# memtester.net
KiCad netlist of a schematic drawn in EAGLE
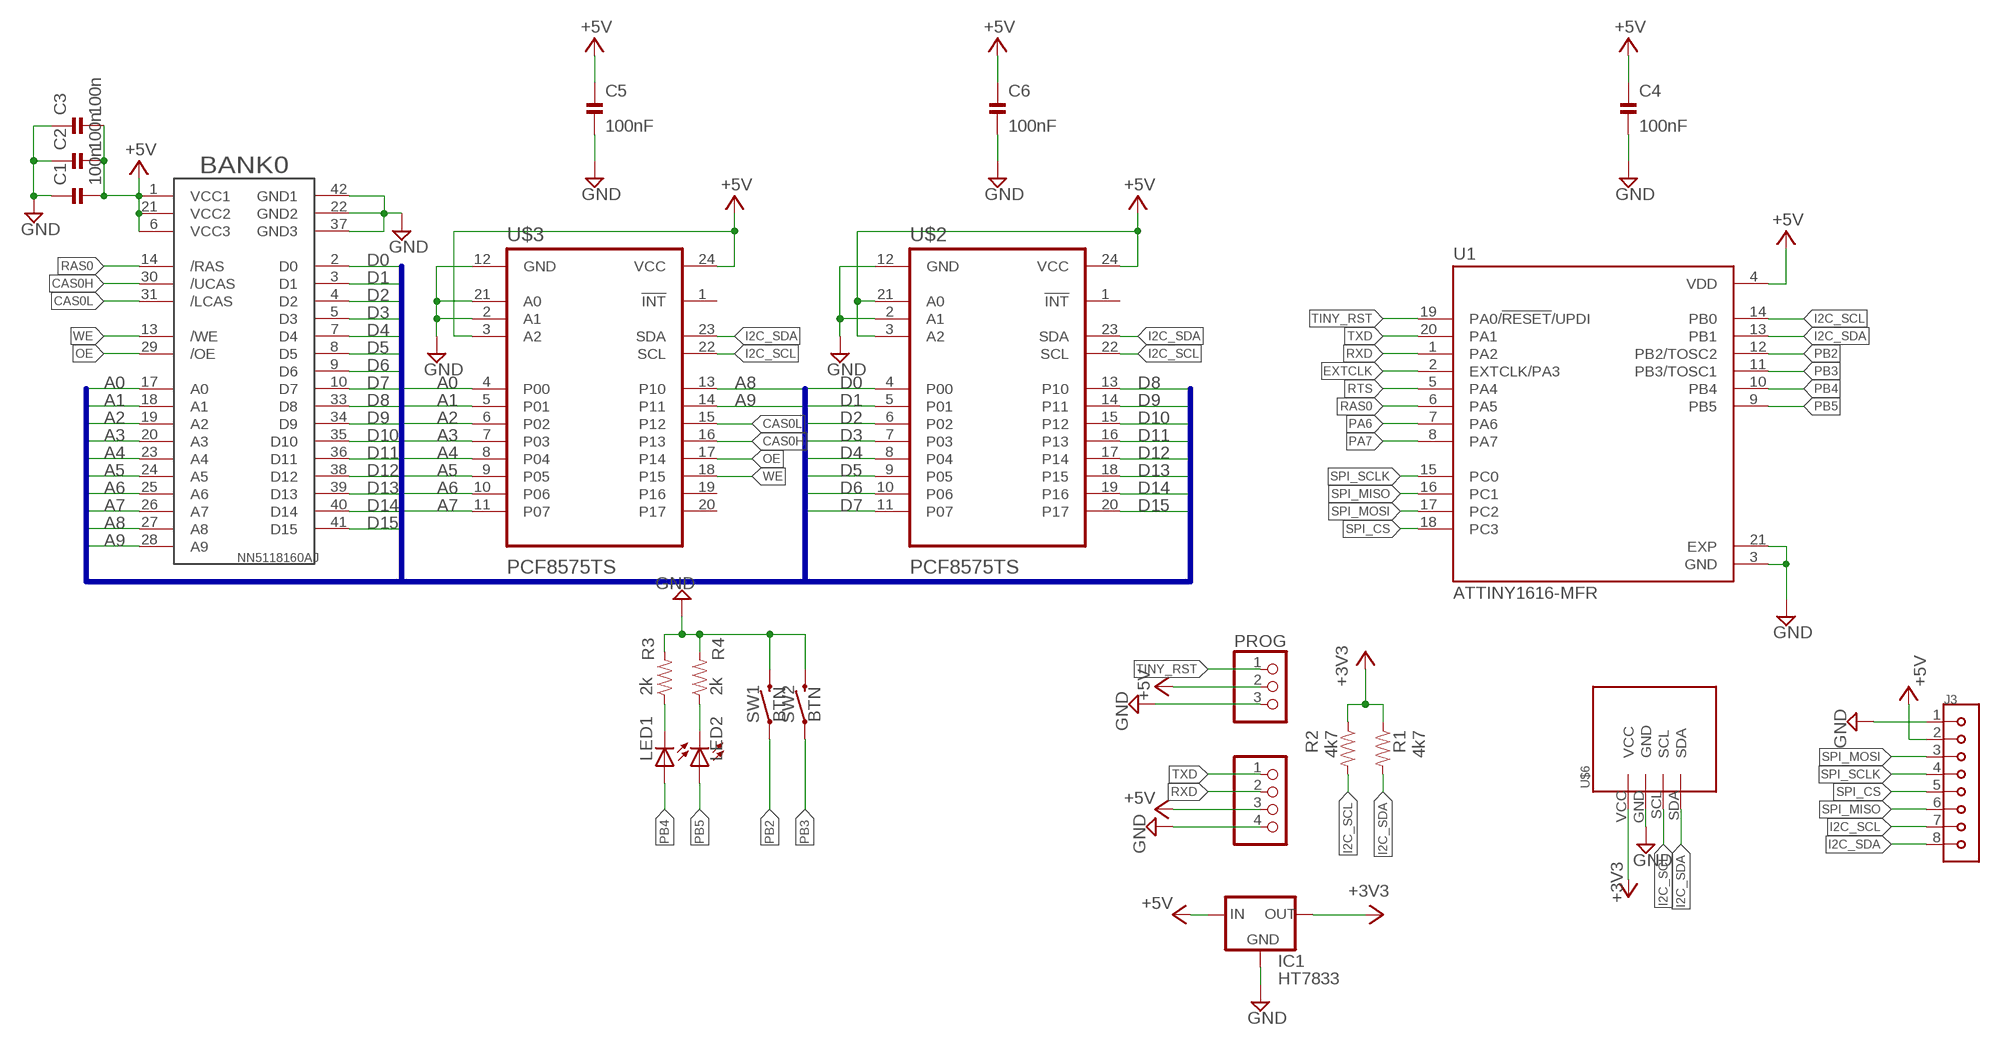
[diagram p0: schematic, sheet 1]

(export (version "E")
  (design (tool "Eeschema 10.0.6"))
  (components
    (comp (ref "C1")
      (value "100n")
      (footprint "eagle-import:0402_CAP")
      (libsource (lib "eagle-import") (part "CAPACITOR0402_CAP"))
    )
    (comp (ref "C2")
      (value "100n")
      (footprint "eagle-import:0402_CAP")
      (libsource (lib "eagle-import") (part "CAPACITOR0402_CAP"))
    )
    (comp (ref "C3")
      (value "100n")
      (footprint "eagle-import:0402_CAP")
      (libsource (lib "eagle-import") (part "CAPACITOR0402_CAP"))
    )
    (comp (ref "C4")
      (value "100nF")
      (footprint "eagle-import:0402_CAP")
      (libsource (lib "eagle-import") (part "CAPACITOR0402_CAP"))
    )
    (comp (ref "C5")
      (value "100nF")
      (footprint "eagle-import:0402_CAP")
      (libsource (lib "eagle-import") (part "CAPACITOR0402_CAP"))
    )
    (comp (ref "C6")
      (value "100nF")
      (footprint "eagle-import:0402_CAP")
      (libsource (lib "eagle-import") (part "CAPACITOR0402_CAP"))
    )
    (comp (ref "IC1")
      (value "HT7833")
      (footprint "eagle-import:SOT-89")
      (fields (field (name "LCSC_PART") "C50936"))
      (libsource (lib "eagle-import") (part "HT7333"))
    )
    (comp (ref "J3")
      (value "SM08B-SRSS-TB(LF)(SN)")
      (footprint "eagle-import:JST_SM08B-SRSS-TB(LF)(SN)")
      (fields (field (name "MF") "JST Sales") (field (name "LCSC_PART") "C160407"))
      (libsource (lib "eagle-import") (part "SM08B-SRSS-TB(LF)(SN)"))
    )
    (comp (ref "LED1")
      (value "green")
      (footprint "eagle-import:CHIP-LED0805")
      (fields (field (name "LCSC_PART") "C2297"))
      (libsource (lib "eagle-import") (part "LEDCHIP-LED0805"))
    )
    (comp (ref "LED2")
      (value "green")
      (footprint "eagle-import:CHIP-LED0805")
      (fields (field (name "LCSC_PART") "C2297"))
      (libsource (lib "eagle-import") (part "LEDCHIP-LED0805"))
    )
    (comp (ref "PROG")
      (value "PINHD-1X3")
      (footprint "eagle-import:1X03")
      (libsource (lib "eagle-import") (part "PINHD-1X3"))
    )
    (comp (ref "R1")
      (value "4k7")
      (footprint "eagle-import:0402_RES")
      (libsource (lib "eagle-import") (part "RESISTOR0402_RES"))
    )
    (comp (ref "R2")
      (value "4k7")
      (footprint "eagle-import:0402_RES")
      (libsource (lib "eagle-import") (part "RESISTOR0402_RES"))
    )
    (comp (ref "R3")
      (value "2k")
      (footprint "eagle-import:0402_RES")
      (libsource (lib "eagle-import") (part "RESISTOR0402_RES"))
    )
    (comp (ref "R4")
      (value "2k")
      (footprint "eagle-import:0402_RES")
      (libsource (lib "eagle-import") (part "RESISTOR0402_RES"))
    )
    (comp (ref "SW1")
      (value "BTN")
      (footprint "eagle-import:TACTILE_SWITCH_SMD_6.0X3.5MM")
      (fields (field (name "LCSC_PART") "C118141"))
      (libsource (lib "eagle-import") (part "MOMENTARY-SWITCH-SPST-SMD-6.0X3.5MM"))
    )
    (comp (ref "SW2")
      (value "BTN")
      (footprint "eagle-import:TACTILE_SWITCH_SMD_6.0X3.5MM")
      (fields (field (name "LCSC_PART") "C118141"))
      (libsource (lib "eagle-import") (part "MOMENTARY-SWITCH-SPST-SMD-6.0X3.5MM"))
    )
    (comp (ref "U$1")
      (value "NN5118160AJSOCKET")
      (footprint "eagle-import:SOJ42SOCKET")
      (libsource (lib "eagle-import") (part "NN5118160AJSOCKET"))
    )
    (comp (ref "U$2")
      (value "PCF8575TS")
      (footprint "eagle-import:SSOP24")
      (fields (field (name "LCSC_PART") "C12251"))
      (libsource (lib "eagle-import") (part "PCF8575TS"))
    )
    (comp (ref "U$3")
      (value "PCF8575TS")
      (footprint "eagle-import:SSOP24")
      (fields (field (name "LCSC_PART") "C12251"))
      (libsource (lib "eagle-import") (part "PCF8575TS"))
    )
    (comp (ref "U$6")
      (value "OLED_0.96_I2CNO_DRILL")
      (footprint "eagle-import:OLED_0.96_I2C_NO_DRILL")
      (libsource (lib "eagle-import") (part "OLED_0.96_I2CNO_DRILL"))
    )
    (comp (ref "U1")
      (value "ATTINY1616-MFR")
      (footprint "eagle-import:QFN40P300X300X90-21N")
      (fields (field (name "MF") "Microchip"))
      (libsource (lib "eagle-import") (part "ATTINY1616-MFR"))
    )
    (comp (ref "UART")
      (value "PINHD-1X4")
      (footprint "eagle-import:1X04")
      (libsource (lib "eagle-import") (part "PINHD-1X4"))
    )
  )
  (nets
    (net (code "1") (name "+3V3") (class "Default")
      (node (ref "IC1") (pin "1") (pinfunction "OUT_1") (pintype "passive"))
      (node (ref "R1") (pin "1") (pinfunction "1_1") (pintype "passive"))
      (node (ref "R2") (pin "1") (pinfunction "1_1") (pintype "passive"))
      (node (ref "U$6") (pin "VCC") (pinfunction "VCC_VCC") (pintype "bidirectional"))
    )
    (net (code "2") (name "+5V") (class "Default")
      (node (ref "C1") (pin "2") (pinfunction "2_2") (pintype "bidirectional"))
      (node (ref "C2") (pin "2") (pinfunction "2_2") (pintype "bidirectional"))
      (node (ref "C3") (pin "2") (pinfunction "2_2") (pintype "bidirectional"))
      (node (ref "C4") (pin "1") (pinfunction "1_1") (pintype "bidirectional"))
      (node (ref "C5") (pin "1") (pinfunction "1_1") (pintype "bidirectional"))
      (node (ref "C6") (pin "1") (pinfunction "1_1") (pintype "bidirectional"))
      (node (ref "IC1") (pin "3") (pinfunction "IN_3") (pintype "input"))
      (node (ref "IC1") (pin "4") (pinfunction "IN_4") (pintype "input"))
      (node (ref "J3") (pin "2") (pinfunction "2_2") (pintype "passive"))
      (node (ref "PROG") (pin "2") (pinfunction "2_2") (pintype "passive"))
      (node (ref "U$1") (pin "1") (pinfunction "VCC1_1") (pintype "bidirectional"))
      (node (ref "U$1") (pin "21") (pinfunction "VCC2_21") (pintype "bidirectional"))
      (node (ref "U$1") (pin "6") (pinfunction "VCC3_6") (pintype "bidirectional"))
      (node (ref "U$2") (pin "21") (pinfunction "A0_21") (pintype "input"))
      (node (ref "U$2") (pin "24") (pinfunction "VCC_24") (pintype "power_in"))
      (node (ref "U$2") (pin "3") (pinfunction "A2_3") (pintype "input"))
      (node (ref "U$3") (pin "24") (pinfunction "VCC_24") (pintype "power_in"))
      (node (ref "U$3") (pin "3") (pinfunction "A2_3") (pintype "input"))
      (node (ref "U1") (pin "4") (pinfunction "VDD_4") (pintype "power_in"))
      (node (ref "UART") (pin "3") (pinfunction "3_3") (pintype "passive"))
    )
    (net (code "3") (name "/A0") (class "Default")
      (node (ref "U$1") (pin "17") (pinfunction "A0_17") (pintype "bidirectional"))
      (node (ref "U$3") (pin "4") (pinfunction "P00_4") (pintype "bidirectional"))
    )
    (net (code "4") (name "/A1") (class "Default")
      (node (ref "U$1") (pin "18") (pinfunction "A1_18") (pintype "bidirectional"))
      (node (ref "U$3") (pin "5") (pinfunction "P01_5") (pintype "bidirectional"))
    )
    (net (code "5") (name "/A2") (class "Default")
      (node (ref "U$1") (pin "19") (pinfunction "A2_19") (pintype "bidirectional"))
      (node (ref "U$3") (pin "6") (pinfunction "P02_6") (pintype "bidirectional"))
    )
    (net (code "6") (name "/A3") (class "Default")
      (node (ref "U$1") (pin "20") (pinfunction "A3_20") (pintype "bidirectional"))
      (node (ref "U$3") (pin "7") (pinfunction "P03_7") (pintype "bidirectional"))
    )
    (net (code "7") (name "/A4") (class "Default")
      (node (ref "U$1") (pin "23") (pinfunction "A4_23") (pintype "bidirectional"))
      (node (ref "U$3") (pin "8") (pinfunction "P04_8") (pintype "bidirectional"))
    )
    (net (code "8") (name "/A5") (class "Default")
      (node (ref "U$1") (pin "24") (pinfunction "A5_24") (pintype "bidirectional"))
      (node (ref "U$3") (pin "9") (pinfunction "P05_9") (pintype "bidirectional"))
    )
    (net (code "9") (name "/A6") (class "Default")
      (node (ref "U$1") (pin "25") (pinfunction "A6_25") (pintype "bidirectional"))
      (node (ref "U$3") (pin "10") (pinfunction "P06_10") (pintype "bidirectional"))
    )
    (net (code "10") (name "/A7") (class "Default")
      (node (ref "U$1") (pin "26") (pinfunction "A7_26") (pintype "bidirectional"))
      (node (ref "U$3") (pin "11") (pinfunction "P07_11") (pintype "bidirectional"))
    )
    (net (code "11") (name "/A8") (class "Default")
      (node (ref "U$1") (pin "27") (pinfunction "A8_27") (pintype "bidirectional"))
      (node (ref "U$3") (pin "13") (pinfunction "P10_13") (pintype "bidirectional"))
    )
    (net (code "12") (name "/A9") (class "Default")
      (node (ref "U$1") (pin "28") (pinfunction "A9_28") (pintype "bidirectional"))
      (node (ref "U$3") (pin "14") (pinfunction "P11_14") (pintype "bidirectional"))
    )
    (net (code "13") (name "/D0") (class "Default")
      (node (ref "U$1") (pin "2") (pinfunction "D0_2") (pintype "bidirectional"))
      (node (ref "U$2") (pin "4") (pinfunction "P00_4") (pintype "bidirectional"))
    )
    (net (code "14") (name "/D1") (class "Default")
      (node (ref "U$1") (pin "3") (pinfunction "D1_3") (pintype "bidirectional"))
      (node (ref "U$2") (pin "5") (pinfunction "P01_5") (pintype "bidirectional"))
    )
    (net (code "15") (name "/D2") (class "Default")
      (node (ref "U$1") (pin "4") (pinfunction "D2_4") (pintype "bidirectional"))
      (node (ref "U$2") (pin "6") (pinfunction "P02_6") (pintype "bidirectional"))
    )
    (net (code "16") (name "/D3") (class "Default")
      (node (ref "U$1") (pin "5") (pinfunction "D3_5") (pintype "bidirectional"))
      (node (ref "U$2") (pin "7") (pinfunction "P03_7") (pintype "bidirectional"))
    )
    (net (code "17") (name "/D4") (class "Default")
      (node (ref "U$1") (pin "7") (pinfunction "D4_7") (pintype "bidirectional"))
      (node (ref "U$2") (pin "8") (pinfunction "P04_8") (pintype "bidirectional"))
    )
    (net (code "18") (name "/D5") (class "Default")
      (node (ref "U$1") (pin "8") (pinfunction "D5_8") (pintype "bidirectional"))
      (node (ref "U$2") (pin "9") (pinfunction "P05_9") (pintype "bidirectional"))
    )
    (net (code "19") (name "/D6") (class "Default")
      (node (ref "U$1") (pin "9") (pinfunction "D6_9") (pintype "bidirectional"))
      (node (ref "U$2") (pin "10") (pinfunction "P06_10") (pintype "bidirectional"))
    )
    (net (code "20") (name "/D7") (class "Default")
      (node (ref "U$1") (pin "10") (pinfunction "D7_10") (pintype "bidirectional"))
      (node (ref "U$2") (pin "11") (pinfunction "P07_11") (pintype "bidirectional"))
    )
    (net (code "21") (name "/D8") (class "Default")
      (node (ref "U$1") (pin "33") (pinfunction "D8_33") (pintype "bidirectional"))
      (node (ref "U$2") (pin "13") (pinfunction "P10_13") (pintype "bidirectional"))
    )
    (net (code "22") (name "/D9") (class "Default")
      (node (ref "U$1") (pin "34") (pinfunction "D9_34") (pintype "bidirectional"))
      (node (ref "U$2") (pin "14") (pinfunction "P11_14") (pintype "bidirectional"))
    )
    (net (code "23") (name "/D10") (class "Default")
      (node (ref "U$1") (pin "35") (pinfunction "D10_35") (pintype "bidirectional"))
      (node (ref "U$2") (pin "15") (pinfunction "P12_15") (pintype "bidirectional"))
    )
    (net (code "24") (name "/D11") (class "Default")
      (node (ref "U$1") (pin "36") (pinfunction "D11_36") (pintype "bidirectional"))
      (node (ref "U$2") (pin "16") (pinfunction "P13_16") (pintype "bidirectional"))
    )
    (net (code "25") (name "/D12") (class "Default")
      (node (ref "U$1") (pin "38") (pinfunction "D12_38") (pintype "bidirectional"))
      (node (ref "U$2") (pin "17") (pinfunction "P14_17") (pintype "bidirectional"))
    )
    (net (code "26") (name "/D13") (class "Default")
      (node (ref "U$1") (pin "39") (pinfunction "D13_39") (pintype "bidirectional"))
      (node (ref "U$2") (pin "18") (pinfunction "P15_18") (pintype "bidirectional"))
    )
    (net (code "27") (name "/D14") (class "Default")
      (node (ref "U$1") (pin "40") (pinfunction "D14_40") (pintype "bidirectional"))
      (node (ref "U$2") (pin "19") (pinfunction "P16_19") (pintype "bidirectional"))
    )
    (net (code "28") (name "/D15") (class "Default")
      (node (ref "U$1") (pin "41") (pinfunction "D15_41") (pintype "bidirectional"))
      (node (ref "U$2") (pin "20") (pinfunction "P17_20") (pintype "bidirectional"))
    )
    (net (code "29") (name "CAS0H") (class "Default")
      (node (ref "U$1") (pin "30") (pinfunction "/UCAS_30") (pintype "bidirectional"))
      (node (ref "U$3") (pin "16") (pinfunction "P13_16") (pintype "bidirectional"))
    )
    (net (code "30") (name "CAS0L") (class "Default")
      (node (ref "U$1") (pin "31") (pinfunction "/LCAS_31") (pintype "bidirectional"))
      (node (ref "U$3") (pin "15") (pinfunction "P12_15") (pintype "bidirectional"))
    )
    (net (code "31") (name "EXTCLK") (class "Default")
      (node (ref "U1") (pin "2") (pinfunction "EXTCLK/PA3_2") (pintype "bidirectional"))
    )
    (net (code "32") (name "GND") (class "Default")
      (node (ref "C1") (pin "1") (pinfunction "1_1") (pintype "bidirectional"))
      (node (ref "C2") (pin "1") (pinfunction "1_1") (pintype "bidirectional"))
      (node (ref "C3") (pin "1") (pinfunction "1_1") (pintype "bidirectional"))
      (node (ref "C4") (pin "2") (pinfunction "2_2") (pintype "bidirectional"))
      (node (ref "C5") (pin "2") (pinfunction "2_2") (pintype "bidirectional"))
      (node (ref "C6") (pin "2") (pinfunction "2_2") (pintype "bidirectional"))
      (node (ref "IC1") (pin "2") (pinfunction "GND_2") (pintype "input"))
      (node (ref "J3") (pin "1") (pinfunction "1_1") (pintype "passive"))
      (node (ref "PROG") (pin "3") (pinfunction "3_3") (pintype "passive"))
      (node (ref "R3") (pin "2") (pinfunction "2_2") (pintype "passive"))
      (node (ref "R4") (pin "2") (pinfunction "2_2") (pintype "passive"))
      (node (ref "SW1") (pin "2") (pinfunction "2_2") (pintype "passive"))
      (node (ref "SW2") (pin "2") (pinfunction "2_2") (pintype "passive"))
      (node (ref "U$1") (pin "22") (pinfunction "GND2_22") (pintype "bidirectional"))
      (node (ref "U$1") (pin "37") (pinfunction "GND3_37") (pintype "bidirectional"))
      (node (ref "U$1") (pin "42") (pinfunction "GND1_42") (pintype "bidirectional"))
      (node (ref "U$2") (pin "12") (pinfunction "GND_12") (pintype "power_in"))
      (node (ref "U$2") (pin "2") (pinfunction "A1_2") (pintype "input"))
      (node (ref "U$3") (pin "12") (pinfunction "GND_12") (pintype "power_in"))
      (node (ref "U$3") (pin "2") (pinfunction "A1_2") (pintype "input"))
      (node (ref "U$3") (pin "21") (pinfunction "A0_21") (pintype "input"))
      (node (ref "U$6") (pin "GND") (pinfunction "GND_GND") (pintype "bidirectional"))
      (node (ref "U1") (pin "21") (pinfunction "EXP_21") (pintype "power_in"))
      (node (ref "U1") (pin "3") (pinfunction "GND_3") (pintype "power_in"))
      (node (ref "UART") (pin "4") (pinfunction "4_4") (pintype "passive"))
    )
    (net (code "33") (name "I2C_SCL") (class "Default")
      (node (ref "J3") (pin "7") (pinfunction "7_7") (pintype "passive"))
      (node (ref "R2") (pin "2") (pinfunction "2_2") (pintype "passive"))
      (node (ref "U$2") (pin "22") (pinfunction "SCL_22") (pintype "input"))
      (node (ref "U$3") (pin "22") (pinfunction "SCL_22") (pintype "input"))
      (node (ref "U$6") (pin "SCL") (pinfunction "SCL_SCL") (pintype "bidirectional"))
      (node (ref "U1") (pin "14") (pinfunction "PB0_14") (pintype "bidirectional"))
    )
    (net (code "34") (name "I2C_SDA") (class "Default")
      (node (ref "J3") (pin "8") (pinfunction "8_8") (pintype "passive"))
      (node (ref "R1") (pin "2") (pinfunction "2_2") (pintype "passive"))
      (node (ref "U$2") (pin "23") (pinfunction "SDA_23") (pintype "bidirectional"))
      (node (ref "U$3") (pin "23") (pinfunction "SDA_23") (pintype "bidirectional"))
      (node (ref "U$6") (pin "SDA") (pinfunction "SDA_SDA") (pintype "bidirectional"))
      (node (ref "U1") (pin "13") (pinfunction "PB1_13") (pintype "bidirectional"))
    )
    (net (code "35") (name "Net-(LED1-PadC)") (class "Default")
      (node (ref "LED1") (pin "C") (pinfunction "C_C") (pintype "passive"))
      (node (ref "R3") (pin "1") (pinfunction "1_1") (pintype "passive"))
    )
    (net (code "36") (name "Net-(LED2-PadC)") (class "Default")
      (node (ref "LED2") (pin "C") (pinfunction "C_C") (pintype "passive"))
      (node (ref "R4") (pin "1") (pinfunction "1_1") (pintype "passive"))
    )
    (net (code "37") (name "OE") (class "Default")
      (node (ref "U$1") (pin "29") (pinfunction "/OE_29") (pintype "bidirectional"))
      (node (ref "U$3") (pin "17") (pinfunction "P14_17") (pintype "bidirectional"))
    )
    (net (code "38") (name "PA6") (class "Default")
      (node (ref "U1") (pin "7") (pinfunction "PA6_7") (pintype "bidirectional"))
    )
    (net (code "39") (name "PA7") (class "Default")
      (node (ref "U1") (pin "8") (pinfunction "PA7_8") (pintype "bidirectional"))
    )
    (net (code "40") (name "PB2") (class "Default")
      (node (ref "SW1") (pin "1") (pinfunction "1_1") (pintype "passive"))
      (node (ref "U1") (pin "12") (pinfunction "PB2/TOSC2_12") (pintype "bidirectional"))
    )
    (net (code "41") (name "PB3") (class "Default")
      (node (ref "SW2") (pin "1") (pinfunction "1_1") (pintype "passive"))
      (node (ref "U1") (pin "11") (pinfunction "PB3/TOSC1_11") (pintype "bidirectional"))
    )
    (net (code "42") (name "PB4") (class "Default")
      (node (ref "LED1") (pin "A") (pinfunction "A_A") (pintype "passive"))
      (node (ref "U1") (pin "10") (pinfunction "PB4_10") (pintype "bidirectional"))
    )
    (net (code "43") (name "PB5") (class "Default")
      (node (ref "LED2") (pin "A") (pinfunction "A_A") (pintype "passive"))
      (node (ref "U1") (pin "9") (pinfunction "PB5_9") (pintype "bidirectional"))
    )
    (net (code "44") (name "RAS0") (class "Default")
      (node (ref "U$1") (pin "14") (pinfunction "/RAS_14") (pintype "bidirectional"))
      (node (ref "U1") (pin "6") (pinfunction "PA5_6") (pintype "bidirectional"))
    )
    (net (code "45") (name "RTS") (class "Default")
      (node (ref "U1") (pin "5") (pinfunction "PA4_5") (pintype "bidirectional"))
    )
    (net (code "46") (name "RXD") (class "Default")
      (node (ref "U1") (pin "1") (pinfunction "PA2_1") (pintype "bidirectional"))
      (node (ref "UART") (pin "2") (pinfunction "2_2") (pintype "passive"))
    )
    (net (code "47") (name "SPI_CS") (class "Default")
      (node (ref "J3") (pin "5") (pinfunction "5_5") (pintype "passive"))
      (node (ref "U1") (pin "18") (pinfunction "PC3_18") (pintype "bidirectional"))
    )
    (net (code "48") (name "SPI_MISO") (class "Default")
      (node (ref "J3") (pin "6") (pinfunction "6_6") (pintype "passive"))
      (node (ref "U1") (pin "16") (pinfunction "PC1_16") (pintype "bidirectional"))
    )
    (net (code "49") (name "SPI_MOSI") (class "Default")
      (node (ref "J3") (pin "3") (pinfunction "3_3") (pintype "passive"))
      (node (ref "U1") (pin "17") (pinfunction "PC2_17") (pintype "bidirectional"))
    )
    (net (code "50") (name "SPI_SCLK") (class "Default")
      (node (ref "J3") (pin "4") (pinfunction "4_4") (pintype "passive"))
      (node (ref "U1") (pin "15") (pinfunction "PC0_15") (pintype "bidirectional"))
    )
    (net (code "51") (name "TINY_RST") (class "Default")
      (node (ref "PROG") (pin "1") (pinfunction "1_1") (pintype "passive"))
      (node (ref "U1") (pin "19") (pinfunction "PA0/~{RESET}/UPDI_19") (pintype "bidirectional"))
    )
    (net (code "52") (name "TXD") (class "Default")
      (node (ref "U1") (pin "20") (pinfunction "PA1_20") (pintype "bidirectional"))
      (node (ref "UART") (pin "1") (pinfunction "1_1") (pintype "passive"))
    )
    (net (code "53") (name "WE") (class "Default")
      (node (ref "U$1") (pin "13") (pinfunction "/WE_13") (pintype "bidirectional"))
      (node (ref "U$3") (pin "18") (pinfunction "P15_18") (pintype "bidirectional"))
    )
    (net (code "54") (name "unconnected-(U$2-~{INT}-Pad1)") (class "Default")
      (node (ref "U$2") (pin "1") (pinfunction "~{INT}_1") (pintype "output"))
    )
    (net (code "55") (name "unconnected-(U$3-P16-Pad19)") (class "Default")
      (node (ref "U$3") (pin "19") (pinfunction "P16_19") (pintype "bidirectional"))
    )
    (net (code "56") (name "unconnected-(U$3-P17-Pad20)") (class "Default")
      (node (ref "U$3") (pin "20") (pinfunction "P17_20") (pintype "bidirectional"))
    )
    (net (code "57") (name "unconnected-(U$3-~{INT}-Pad1)") (class "Default")
      (node (ref "U$3") (pin "1") (pinfunction "~{INT}_1") (pintype "output"))
    )
  )
)
